# FEEL_2021_sensors.net
KiCad netlist of a schematic drawn in Altium Designer
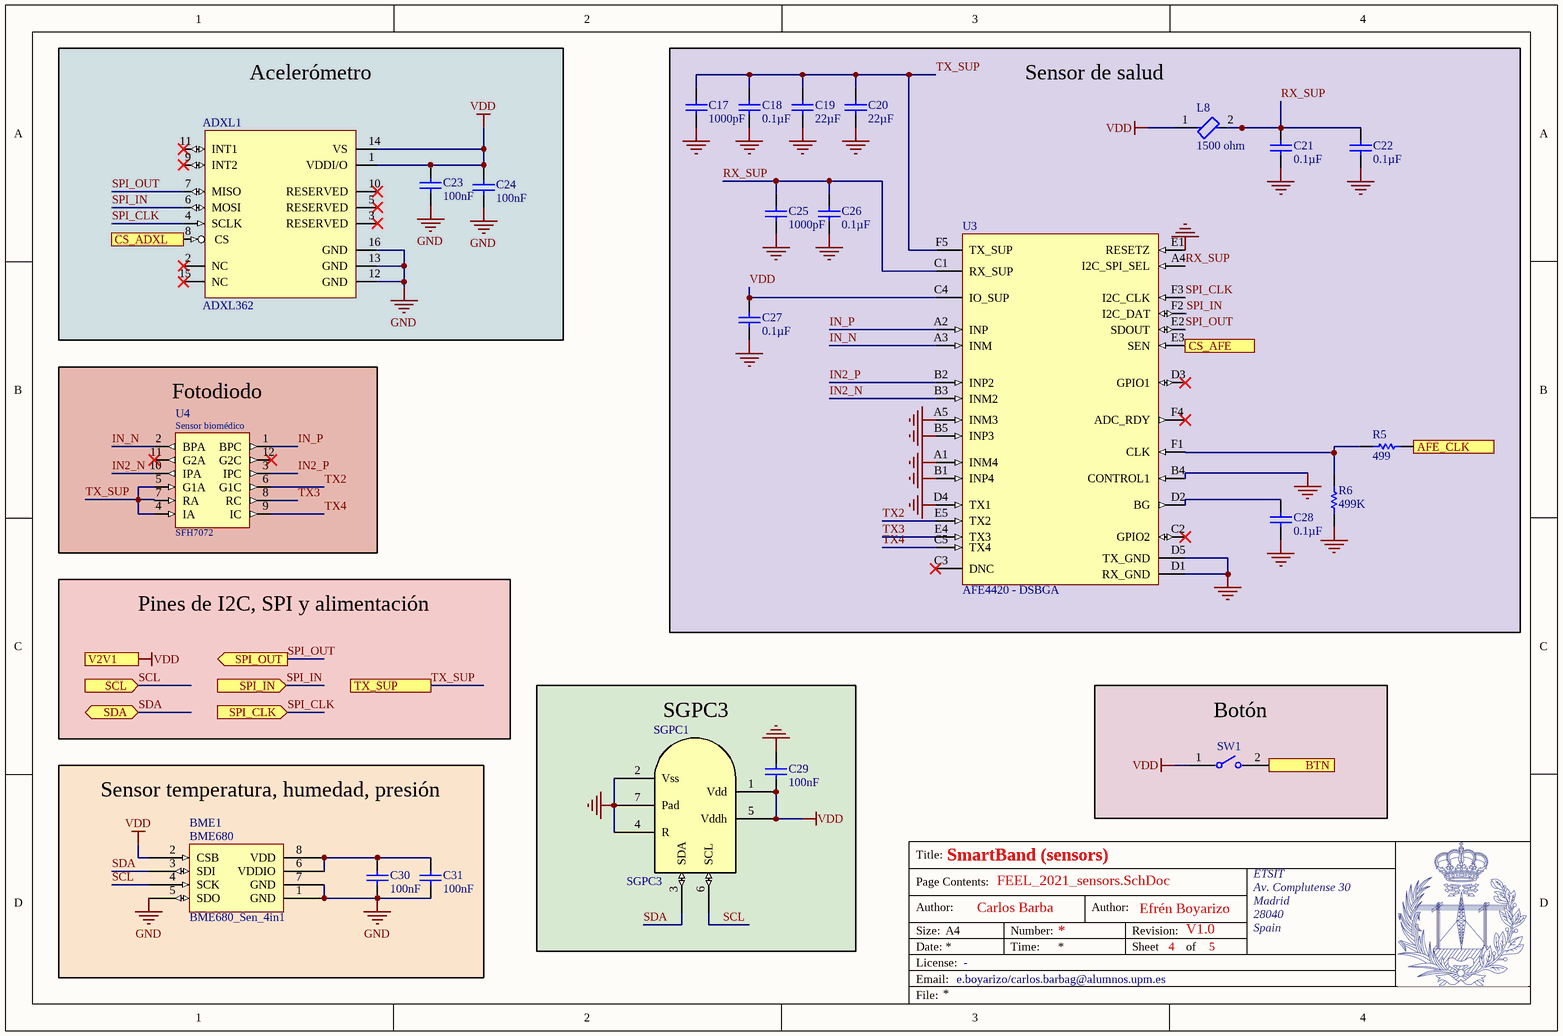
[diagram p0: FEEL_2021_sensors.SchDoc]

(export (version "E")
  (design (tool "Eeschema 10.0.6"))
  (components
    (comp (ref "ADXL1")
      (value "~")
      (footprint "ADXL362 - duplicate")
      (libsource (lib "FEEL2122") (part "ADXL362"))
    )
    (comp (ref "BME1")
      (value "BME680_Sen_4in1")
      (footprint "BME_LGA8")
      (libsource (lib "FEEL2122") (part "BME680_Sen_4in1"))
    )
    (comp (ref "C17")
      (value "1000pF")
      (footprint "CAPC1608X90X35ML10T15")
      (description "Chip Capacitor, 22 pF, +/- 5%, 50 V, -55 to 125 degC, 0603 (1608 Metric), RoHS, Tape and Reel")
      (fields (field (name "MANUFACTURER") "Murata"))
      (libsource (lib "Altium Content Vault") (part "CAP-NP-2"))
    )
    (comp (ref "C18")
      (value "0.1µF")
      (footprint "CAPC1608X90X35ML10T15")
      (description "Chip Capacitor, 22 pF, +/- 5%, 50 V, -55 to 125 degC, 0603 (1608 Metric), RoHS, Tape and Reel")
      (fields (field (name "MANUFACTURER") "Murata"))
      (libsource (lib "Altium Content Vault") (part "CAP-NP-2"))
    )
    (comp (ref "C19")
      (value "22µF")
      (footprint "CAPC1608X90X35ML10T15")
      (description "Chip Capacitor, 22 pF, +/- 5%, 50 V, -55 to 125 degC, 0603 (1608 Metric), RoHS, Tape and Reel")
      (fields (field (name "MANUFACTURER") "Murata"))
      (libsource (lib "Altium Content Vault") (part "CAP-NP-2"))
    )
    (comp (ref "C20")
      (value "22µF")
      (footprint "CAPC1608X90X35ML10T15")
      (description "Chip Capacitor, 22 pF, +/- 5%, 50 V, -55 to 125 degC, 0603 (1608 Metric), RoHS, Tape and Reel")
      (fields (field (name "MANUFACTURER") "Murata"))
      (libsource (lib "Altium Content Vault") (part "CAP-NP-2"))
    )
    (comp (ref "C21")
      (value "0.1µF")
      (footprint "CAPC1608X90X35ML10T15")
      (description "Chip Capacitor, 22 pF, +/- 5%, 50 V, -55 to 125 degC, 0603 (1608 Metric), RoHS, Tape and Reel")
      (fields (field (name "MANUFACTURER") "Murata"))
      (libsource (lib "Altium Content Vault") (part "CAP-NP-2"))
    )
    (comp (ref "C22")
      (value "0.1µF")
      (footprint "CAPC1608X90X35ML10T15")
      (description "Chip Capacitor, 22 pF, +/- 5%, 50 V, -55 to 125 degC, 0603 (1608 Metric), RoHS, Tape and Reel")
      (fields (field (name "MANUFACTURER") "Murata"))
      (libsource (lib "Altium Content Vault") (part "CAP-NP-2"))
    )
    (comp (ref "C23")
      (value "100nF")
      (footprint "CAPC1608X90X35ML10T15")
      (description "Chip Capacitor, 22 pF, +/- 5%, 50 V, -55 to 125 degC, 0603 (1608 Metric), RoHS, Tape and Reel")
      (fields (field (name "MANUFACTURER") "Murata"))
      (libsource (lib "Altium Content Vault") (part "CAP-NP-2"))
    )
    (comp (ref "C24")
      (value "100nF")
      (footprint "CAPC1608X90X35ML10T15")
      (description "Chip Capacitor, 22 pF, +/- 5%, 50 V, -55 to 125 degC, 0603 (1608 Metric), RoHS, Tape and Reel")
      (fields (field (name "MANUFACTURER") "Murata"))
      (libsource (lib "Altium Content Vault") (part "CAP-NP-2"))
    )
    (comp (ref "C25")
      (value "1000pF")
      (footprint "CAPC1608X90X35ML10T15")
      (description "Chip Capacitor, 22 pF, +/- 5%, 50 V, -55 to 125 degC, 0603 (1608 Metric), RoHS, Tape and Reel")
      (fields (field (name "MANUFACTURER") "Murata"))
      (libsource (lib "Altium Content Vault") (part "CAP-NP-2"))
    )
    (comp (ref "C26")
      (value "0.1µF")
      (footprint "CAPC1608X90X35ML10T15")
      (description "Chip Capacitor, 22 pF, +/- 5%, 50 V, -55 to 125 degC, 0603 (1608 Metric), RoHS, Tape and Reel")
      (fields (field (name "MANUFACTURER") "Murata"))
      (libsource (lib "Altium Content Vault") (part "CAP-NP-2"))
    )
    (comp (ref "C27")
      (value "0.1µF")
      (footprint "CAPC1608X90X35ML10T15")
      (description "Chip Capacitor, 22 pF, +/- 5%, 50 V, -55 to 125 degC, 0603 (1608 Metric), RoHS, Tape and Reel")
      (fields (field (name "MANUFACTURER") "Murata"))
      (libsource (lib "Altium Content Vault") (part "CAP-NP-2"))
    )
    (comp (ref "C28")
      (value "0.1µF")
      (footprint "CAPC1608X90X35ML10T15")
      (description "Chip Capacitor, 22 pF, +/- 5%, 50 V, -55 to 125 degC, 0603 (1608 Metric), RoHS, Tape and Reel")
      (fields (field (name "MANUFACTURER") "Murata"))
      (libsource (lib "Altium Content Vault") (part "CAP-NP-2"))
    )
    (comp (ref "C29")
      (value "100nF")
      (footprint "CAPC1608X90X35ML10T15")
      (description "Chip Capacitor, 22 pF, +/- 5%, 50 V, -55 to 125 degC, 0603 (1608 Metric), RoHS, Tape and Reel")
      (fields (field (name "MANUFACTURER") "Murata"))
      (libsource (lib "Altium Content Vault") (part "CAP-NP-2"))
    )
    (comp (ref "C30")
      (value "100nF")
      (footprint "CAPC1608X90X35ML10T15")
      (description "Chip Capacitor, 22 pF, +/- 5%, 50 V, -55 to 125 degC, 0603 (1608 Metric), RoHS, Tape and Reel")
      (fields (field (name "MANUFACTURER") "Murata"))
      (libsource (lib "Altium Content Vault") (part "CAP-NP-2"))
    )
    (comp (ref "C31")
      (value "100nF")
      (footprint "CAPC1608X90X35ML10T15")
      (description "Chip Capacitor, 22 pF, +/- 5%, 50 V, -55 to 125 degC, 0603 (1608 Metric), RoHS, Tape and Reel")
      (fields (field (name "MANUFACTURER") "Murata"))
      (libsource (lib "Altium Content Vault") (part "CAP-NP-2"))
    )
    (comp (ref "L8")
      (value "1500 ohm")
      (footprint "FP-BLM18-0_15-t0_8-MFG")
      (description "Chip Ferrite Bead, 0603, 600Ω @ 100MHz, 0.35Ω, 25%, 500mA")
      (fields (field (name "TOLERANCE") "25%"))
      (libsource (lib "Altium Content Vault") (part "5f30dd21d616792df468990f7003faa"))
    )
    (comp (ref "R5")
      (value "499")
      (footprint "RESC1609X50X30NL8T20")
      (description "Chip Resistor, 0 Ohm, Jumper, 100 mW, -55 to 155 degC, 0603 (1608 Metric), RoHS, Tape and Reel")
      (fields (field (name "MANUFACTURER") "Vishay Semiconductor"))
      (libsource (lib "Altium Content Vault") (part "RES-2"))
    )
    (comp (ref "R6")
      (value "499K")
      (footprint "RESC1609X50X30NL8T20")
      (description "Chip Resistor, 0 Ohm, Jumper, 100 mW, -55 to 155 degC, 0603 (1608 Metric), RoHS, Tape and Reel")
      (fields (field (name "MANUFACTURER") "Vishay Semiconductor"))
      (libsource (lib "Altium Content Vault") (part "RES-2"))
    )
    (comp (ref "SGPC1")
      (value "SGPC3")
      (footprint "DFN 6-pin")
      (description "Indoor Air Quality Sensor for TVOC Measurements")
      (libsource (lib "FEEL2122") (part "SGPC3"))
    )
    (comp (ref "SW1")
      (value "~")
      (footprint "FP-B3U-1000P-MFG")
      (description "SWITCH TACTILE SPST-NO 0.05A 12V")
      (libsource (lib "Altium Content Vault") (part "ae622034201233ca1abcedc05908f33"))
    )
    (comp (ref "U3")
      (value "AFE4420 - DSBGA")
      (footprint "AFE4420 - DSBGA")
      (libsource (lib "FEEL2122") (part "AFE4420 - DSBGA"))
    )
    (comp (ref "U4")
      (value "~")
      (footprint "SFH7072")
      (description "Sensor biométrico")
      (libsource (lib "FEEL2122") (part "SFH7072"))
    )
  )
  (nets
    (net (code "1") (name "/AFE_CLK") (class "Default")
      (node (ref "R5") (pin "1") (pinfunction "1_1") (pintype "passive"))
    )
    (net (code "2") (name "/BTN") (class "Default")
      (node (ref "SW1") (pin "2") (pinfunction "2_2") (pintype "passive"))
    )
    (net (code "3") (name "/CS_ADXL") (class "Default")
      (node (ref "ADXL1") (pin "8") (pinfunction "CS_8") (pintype "input"))
    )
    (net (code "4") (name "/CS_AFE") (class "Default")
      (node (ref "U3") (pin "E3") (pinfunction "SEN_E3") (pintype "input"))
    )
    (net (code "5") (name "/IN2_N") (class "Default")
      (node (ref "U3") (pin "B3") (pinfunction "INM2_B3") (pintype "input"))
      (node (ref "U4") (pin "10") (pinfunction "IPA_10") (pintype "output"))
    )
    (net (code "6") (name "/IN2_P") (class "Default")
      (node (ref "U3") (pin "B2") (pinfunction "INP2_B2") (pintype "input"))
      (node (ref "U4") (pin "3") (pinfunction "IPC_3") (pintype "output"))
    )
    (net (code "7") (name "/IN_N") (class "Default")
      (node (ref "U3") (pin "A3") (pinfunction "INM_A3") (pintype "input"))
      (node (ref "U4") (pin "2") (pinfunction "BPA_2") (pintype "output"))
    )
    (net (code "8") (name "/IN_P") (class "Default")
      (node (ref "U3") (pin "A2") (pinfunction "INP_A2") (pintype "input"))
      (node (ref "U4") (pin "1") (pinfunction "BPC_1") (pintype "output"))
    )
    (net (code "9") (name "/RX_SUP") (class "Default")
      (node (ref "C21") (pin "2") (pinfunction "2_2") (pintype "passive"))
      (node (ref "C22") (pin "2") (pinfunction "2_2") (pintype "passive"))
      (node (ref "C25") (pin "2") (pinfunction "2_2") (pintype "passive"))
      (node (ref "C26") (pin "2") (pinfunction "2_2") (pintype "passive"))
      (node (ref "L8") (pin "2") (pinfunction "2_2") (pintype "passive"))
      (node (ref "U3") (pin "A4") (pinfunction "I2C_SPI_SEL_A4") (pintype "input"))
      (node (ref "U3") (pin "C1") (pinfunction "RX_SUP_C1") (pintype "power_in"))
    )
    (net (code "10") (name "/SCL") (class "Default")
      (node (ref "BME1") (pin "4") (pinfunction "SCK_4") (pintype "input"))
      (node (ref "SGPC1") (pin "6") (pinfunction "SCL_6") (pintype "bidirectional"))
    )
    (net (code "11") (name "/SDA") (class "Default")
      (node (ref "BME1") (pin "3") (pinfunction "SDI_3") (pintype "bidirectional"))
      (node (ref "SGPC1") (pin "3") (pinfunction "SDA_3") (pintype "bidirectional"))
    )
    (net (code "12") (name "/SPI_CLK") (class "Default")
      (node (ref "ADXL1") (pin "4") (pinfunction "SCLK_4") (pintype "input"))
      (node (ref "U3") (pin "F3") (pinfunction "I2C_CLK_F3") (pintype "input"))
    )
    (net (code "13") (name "/SPI_IN") (class "Default")
      (node (ref "ADXL1") (pin "6") (pinfunction "MOSI_6") (pintype "bidirectional"))
      (node (ref "U3") (pin "F2") (pinfunction "I2C_DAT_F2") (pintype "bidirectional"))
    )
    (net (code "14") (name "/SPI_OUT") (class "Default")
      (node (ref "ADXL1") (pin "7") (pinfunction "MISO_7") (pintype "bidirectional"))
      (node (ref "U3") (pin "E2") (pinfunction "SDOUT_E2") (pintype "bidirectional"))
    )
    (net (code "15") (name "/TX2") (class "Default")
      (node (ref "U3") (pin "E5") (pinfunction "TX2_E5") (pintype "input"))
      (node (ref "U4") (pin "6") (pinfunction "G1C_6") (pintype "output"))
    )
    (net (code "16") (name "/TX3") (class "Default")
      (node (ref "U3") (pin "E4") (pinfunction "TX3_E4") (pintype "input"))
      (node (ref "U4") (pin "8") (pinfunction "RC_8") (pintype "output"))
    )
    (net (code "17") (name "/TX4") (class "Default")
      (node (ref "U3") (pin "C5") (pinfunction "TX4_C5") (pintype "input"))
      (node (ref "U4") (pin "9") (pinfunction "IC_9") (pintype "output"))
    )
    (net (code "18") (name "/TX_SUP") (class "Default")
      (node (ref "C17") (pin "2") (pinfunction "2_2") (pintype "passive"))
      (node (ref "C18") (pin "2") (pinfunction "2_2") (pintype "passive"))
      (node (ref "C19") (pin "2") (pinfunction "2_2") (pintype "passive"))
      (node (ref "C20") (pin "2") (pinfunction "2_2") (pintype "passive"))
      (node (ref "U3") (pin "F5") (pinfunction "TX_SUP_F5") (pintype "power_in"))
      (node (ref "U4") (pin "4") (pinfunction "IA_4") (pintype "input"))
      (node (ref "U4") (pin "5") (pinfunction "G1A_5") (pintype "input"))
      (node (ref "U4") (pin "7") (pinfunction "RA_7") (pintype "input"))
    )
    (net (code "19") (name "GND") (class "Default")
      (node (ref "ADXL1") (pin "12") (pinfunction "GND_12") (pintype "power_in"))
      (node (ref "ADXL1") (pin "13") (pinfunction "GND_13") (pintype "power_in"))
      (node (ref "ADXL1") (pin "16") (pinfunction "GND_16") (pintype "power_in"))
      (node (ref "BME1") (pin "1") (pinfunction "GND_1") (pintype "power_in"))
      (node (ref "BME1") (pin "5") (pinfunction "SDO_5") (pintype "bidirectional"))
      (node (ref "BME1") (pin "7") (pinfunction "GND_7") (pintype "power_in"))
      (node (ref "C17") (pin "1") (pinfunction "1_1") (pintype "passive"))
      (node (ref "C18") (pin "1") (pinfunction "1_1") (pintype "passive"))
      (node (ref "C19") (pin "1") (pinfunction "1_1") (pintype "passive"))
      (node (ref "C20") (pin "1") (pinfunction "1_1") (pintype "passive"))
      (node (ref "C21") (pin "1") (pinfunction "1_1") (pintype "passive"))
      (node (ref "C22") (pin "1") (pinfunction "1_1") (pintype "passive"))
      (node (ref "C23") (pin "1") (pinfunction "1_1") (pintype "passive"))
      (node (ref "C24") (pin "1") (pinfunction "1_1") (pintype "passive"))
      (node (ref "C25") (pin "1") (pinfunction "1_1") (pintype "passive"))
      (node (ref "C26") (pin "1") (pinfunction "1_1") (pintype "passive"))
      (node (ref "C27") (pin "1") (pinfunction "1_1") (pintype "passive"))
      (node (ref "C28") (pin "1") (pinfunction "1_1") (pintype "passive"))
      (node (ref "C29") (pin "2") (pinfunction "2_2") (pintype "passive"))
      (node (ref "C30") (pin "1") (pinfunction "1_1") (pintype "passive"))
      (node (ref "C31") (pin "1") (pinfunction "1_1") (pintype "passive"))
      (node (ref "R6") (pin "1") (pinfunction "1_1") (pintype "passive"))
      (node (ref "SGPC1") (pin "2") (pinfunction "Vss_2") (pintype "power_in"))
      (node (ref "SGPC1") (pin "4") (pinfunction "R_4") (pintype "passive"))
      (node (ref "SGPC1") (pin "7") (pinfunction "Pad_7") (pintype "passive"))
      (node (ref "U3") (pin "A1") (pinfunction "INM4_A1") (pintype "input"))
      (node (ref "U3") (pin "A5") (pinfunction "INM3_A5") (pintype "input"))
      (node (ref "U3") (pin "B1") (pinfunction "INP4_B1") (pintype "input"))
      (node (ref "U3") (pin "B4") (pinfunction "CONTROL1_B4") (pintype "input"))
      (node (ref "U3") (pin "B5") (pinfunction "INP3_B5") (pintype "input"))
      (node (ref "U3") (pin "D1") (pinfunction "RX_GND_D1") (pintype "power_in"))
      (node (ref "U3") (pin "D4") (pinfunction "TX1_D4") (pintype "input"))
      (node (ref "U3") (pin "D5") (pinfunction "TX_GND_D5") (pintype "power_in"))
      (node (ref "U3") (pin "E1") (pinfunction "RESETZ_E1") (pintype "input"))
    )
    (net (code "20") (name "Net-(BME1-VDD)") (class "Default")
      (node (ref "BME1") (pin "6") (pinfunction "VDDIO_6") (pintype "power_in"))
      (node (ref "BME1") (pin "8") (pinfunction "VDD_8") (pintype "power_in"))
      (node (ref "C30") (pin "2") (pinfunction "2_2") (pintype "passive"))
      (node (ref "C31") (pin "2") (pinfunction "2_2") (pintype "passive"))
    )
    (net (code "21") (name "Net-(U3-BG)") (class "Default")
      (node (ref "C28") (pin "2") (pinfunction "2_2") (pintype "passive"))
      (node (ref "U3") (pin "D2") (pinfunction "BG_D2") (pintype "output"))
    )
    (net (code "22") (name "Net-(U3-CLK)") (class "Default")
      (node (ref "R5") (pin "2") (pinfunction "2_2") (pintype "passive"))
      (node (ref "R6") (pin "2") (pinfunction "2_2") (pintype "passive"))
      (node (ref "U3") (pin "F1") (pinfunction "CLK_F1") (pintype "input"))
    )
    (net (code "23") (name "VDD") (class "Default")
      (node (ref "ADXL1") (pin "1") (pinfunction "VDDI/O_1") (pintype "power_in"))
      (node (ref "ADXL1") (pin "14") (pinfunction "VS_14") (pintype "power_in"))
      (node (ref "BME1") (pin "2") (pinfunction "CSB_2") (pintype "input"))
      (node (ref "C23") (pin "2") (pinfunction "2_2") (pintype "passive"))
      (node (ref "C24") (pin "2") (pinfunction "2_2") (pintype "passive"))
      (node (ref "C27") (pin "2") (pinfunction "2_2") (pintype "passive"))
      (node (ref "C29") (pin "1") (pinfunction "1_1") (pintype "passive"))
      (node (ref "L8") (pin "1") (pinfunction "1_1") (pintype "passive"))
      (node (ref "SGPC1") (pin "1") (pinfunction "Vdd_1") (pintype "power_in"))
      (node (ref "SGPC1") (pin "5") (pinfunction "Vddh_5") (pintype "power_in"))
      (node (ref "SW1") (pin "1") (pinfunction "1_1") (pintype "passive"))
      (node (ref "U3") (pin "C4") (pinfunction "IO_SUP_C4") (pintype "power_in"))
    )
    (net (code "24") (name "unconnected-(ADXL1-INT1-Pad11)") (class "Default")
      (node (ref "ADXL1") (pin "11") (pinfunction "INT1_11") (pintype "bidirectional+no_connect"))
    )
    (net (code "25") (name "unconnected-(ADXL1-INT2-Pad9)") (class "Default")
      (node (ref "ADXL1") (pin "9") (pinfunction "INT2_9") (pintype "bidirectional+no_connect"))
    )
    (net (code "26") (name "unconnected-(ADXL1-NC-Pad2)") (class "Default")
      (node (ref "ADXL1") (pin "2") (pinfunction "NC_2") (pintype "passive+no_connect"))
    )
    (net (code "27") (name "unconnected-(ADXL1-NC-Pad15)") (class "Default")
      (node (ref "ADXL1") (pin "15") (pinfunction "NC_15") (pintype "passive+no_connect"))
    )
    (net (code "28") (name "unconnected-(ADXL1-RESERVED-Pad3)") (class "Default")
      (node (ref "ADXL1") (pin "3") (pinfunction "RESERVED_3") (pintype "passive+no_connect"))
    )
    (net (code "29") (name "unconnected-(ADXL1-RESERVED-Pad5)") (class "Default")
      (node (ref "ADXL1") (pin "5") (pinfunction "RESERVED_5") (pintype "passive+no_connect"))
    )
    (net (code "30") (name "unconnected-(ADXL1-RESERVED-Pad10)") (class "Default")
      (node (ref "ADXL1") (pin "10") (pinfunction "RESERVED_10") (pintype "passive+no_connect"))
    )
    (net (code "31") (name "unconnected-(U3-ADC_RDY-PadF4)") (class "Default")
      (node (ref "U3") (pin "F4") (pinfunction "ADC_RDY_F4") (pintype "output+no_connect"))
    )
    (net (code "32") (name "unconnected-(U3-DNC-PadC3)") (class "Default")
      (node (ref "U3") (pin "C3") (pinfunction "DNC_C3") (pintype "passive+no_connect"))
    )
    (net (code "33") (name "unconnected-(U3-GPIO1-PadD3)") (class "Default")
      (node (ref "U3") (pin "D3") (pinfunction "GPIO1_D3") (pintype "bidirectional+no_connect"))
    )
    (net (code "34") (name "unconnected-(U3-GPIO2-PadC2)") (class "Default")
      (node (ref "U3") (pin "C2") (pinfunction "GPIO2_C2") (pintype "bidirectional+no_connect"))
    )
    (net (code "35") (name "unconnected-(U4-G2A-Pad11)") (class "Default")
      (node (ref "U4") (pin "11") (pinfunction "G2A_11") (pintype "output+no_connect"))
    )
    (net (code "36") (name "unconnected-(U4-G2C-Pad12)") (class "Default")
      (node (ref "U4") (pin "12") (pinfunction "G2C_12") (pintype "output+no_connect"))
    )
  )
)
